# mipi_deserializer_poc.net
KiCad netlist of a schematic drawn in Altium Designer
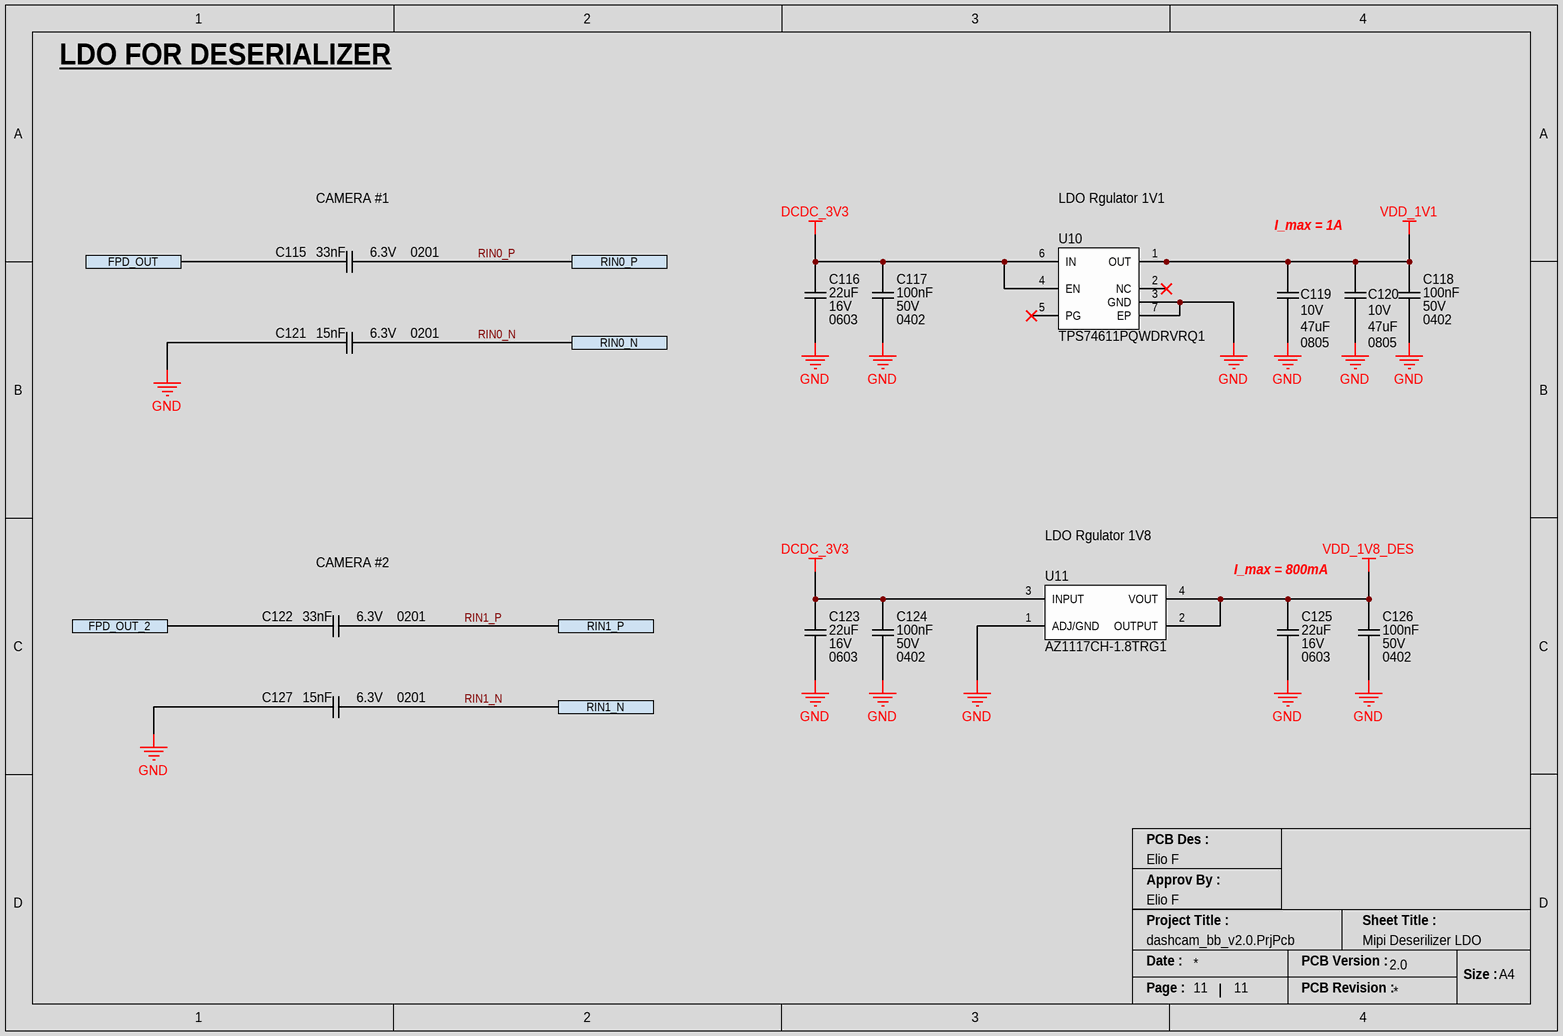
[diagram p0: mipi_deserializer_poc.SchDoc]

(export (version "E")
  (design (tool "Eeschema 10.0.6"))
  (components
    (comp (ref "C115")
      (value "GRM033R60J333KE01D")
      (footprint "CAP_0201_CAPC0603X03N")
      (description "Multilayer Ceramic Capacitor, 0.033 uF, 6.3 V, ± 10%, X5R, 0201 [0603 Metric]")
      (fields
        (field (name "MANUFACTURER") "Murata")
        (field (name "TOLERANCE") "10%")
        (field (name "VOLTAGE RATING") "6.3V")
        (field (name "CAPACITANCE") "33nF")
        (field (name "CASE/PACKAGE") "0201")
      )
      (libsource (lib "Electronic Devices_LIB") (part "CAP_0.033uF_6.3V_X5R_0201"))
    )
    (comp (ref "C116")
      (value "CL10A226MO7JZNC")
      (footprint "CAP_0603_CAPC1608X08N")
      (description "Cap Ceramic 22uF 16V X5R 20% Pad SMD 0603 85C T/R")
      (fields
        (field (name "MANUFACTURER") "Samsung")
        (field (name "TOLERANCE") "20%")
        (field (name "CAPACITANCE") "22uF")
        (field (name "VOLTAGE RATING") "16V")
        (field (name "CASE/PACKAGE") "0603")
      )
      (libsource (lib "Electronic Devices_LIB") (part "CAP_22UF_16V_X5R_0603"))
    )
    (comp (ref "C117")
      (value "GRM155R71H104KE14D")
      (footprint "CAP_0402_CAPC1005X05N")
      (description "Multilayer Ceramic Capacitor, 0.1 uF, 16 V, ± 10%, X7R, 0402 [1005 Metric]")
      (fields
        (field (name "MANUFACTURER") "Murata")
        (field (name "TOLERANCE") "10%")
        (field (name "VOLTAGE RATING") "50V")
        (field (name "CAPACITANCE") "100nF")
        (field (name "CASE/PACKAGE") "0402")
      )
      (libsource (lib "Electronic Devices_LIB") (part "CAP_100NF_50V_X7R_0402"))
    )
    (comp (ref "C118")
      (value "GRM155R71H104KE14D")
      (footprint "CAP_0402_CAPC1005X05N")
      (description "Multilayer Ceramic Capacitor, 0.1 uF, 16 V, ± 10%, X7R, 0402 [1005 Metric]")
      (fields
        (field (name "MANUFACTURER") "Murata")
        (field (name "TOLERANCE") "10%")
        (field (name "VOLTAGE RATING") "50V")
        (field (name "CAPACITANCE") "100nF")
        (field (name "CASE/PACKAGE") "0402")
      )
      (libsource (lib "Electronic Devices_LIB") (part "CAP_100NF_50V_X7R_0402"))
    )
    (comp (ref "C119")
      (value "C2012X5R1A476M125AC")
      (footprint "CAP_0805_CAPC2012X12N")
      (description "Multilayer Ceramic Capacitor, 47 uF, 10 V, ± 20%, X5R, 0805 [2012 Metric]")
      (fields
        (field (name "MANUFACTURER") "TDK")
        (field (name "TOLERANCE") "20%")
        (field (name "VOLTAGE RATING (DC)") "10V")
        (field (name "CAPACITANCE") "47uF")
        (field (name "CASE CODE (IMPERIAL)") "0805")
      )
      (libsource (lib "Electronic Devices_LIB") (part "CAP_47UF_10V_X5R_0805"))
    )
    (comp (ref "C120")
      (value "C2012X5R1A476M125AC")
      (footprint "CAP_0805_CAPC2012X12N")
      (description "Multilayer Ceramic Capacitor, 47 uF, 10 V, ± 20%, X5R, 0805 [2012 Metric]")
      (fields
        (field (name "MANUFACTURER") "TDK")
        (field (name "TOLERANCE") "20%")
        (field (name "VOLTAGE RATING (DC)") "10V")
        (field (name "CAPACITANCE") "47uF")
        (field (name "CASE CODE (IMPERIAL)") "0805")
      )
      (libsource (lib "Electronic Devices_LIB") (part "CAP_47UF_10V_X5R_0805"))
    )
    (comp (ref "C121")
      (value "GRM033R60J153KE01D")
      (footprint "CAP_0201_CAPC0603X03N")
      (description "0201 15 nF 6.3 V ±10% Tolerance X5R SMT Multilayer Ceramic Capacitor")
      (fields
        (field (name "MANUFACTURER") "Murata")
        (field (name "TOLERANCE") "10%")
        (field (name "VOLTAGE RATING") "6.3V")
        (field (name "CAPACITANCE") "15nF")
        (field (name "CASE/PACKAGE") "0201")
      )
      (libsource (lib "Electronic Devices_LIB") (part "CAP_0.015uF_6.3V_X5R_0201"))
    )
    (comp (ref "C122")
      (value "GRM033R60J333KE01D")
      (footprint "CAP_0201_CAPC0603X03N")
      (description "Multilayer Ceramic Capacitor, 0.033 uF, 6.3 V, ± 10%, X5R, 0201 [0603 Metric]")
      (fields
        (field (name "MANUFACTURER") "Murata")
        (field (name "TOLERANCE") "10%")
        (field (name "VOLTAGE RATING") "6.3V")
        (field (name "CAPACITANCE") "33nF")
        (field (name "CASE/PACKAGE") "0201")
      )
      (libsource (lib "Electronic Devices_LIB") (part "CAP_0.033uF_6.3V_X5R_0201"))
    )
    (comp (ref "C123")
      (value "CL10A226MO7JZNC")
      (footprint "CAP_0603_CAPC1608X08N")
      (description "Cap Ceramic 22uF 16V X5R 20% Pad SMD 0603 85C T/R")
      (fields
        (field (name "MANUFACTURER") "Samsung")
        (field (name "TOLERANCE") "20%")
        (field (name "CAPACITANCE") "22uF")
        (field (name "VOLTAGE RATING") "16V")
        (field (name "CASE/PACKAGE") "0603")
      )
      (libsource (lib "Electronic Devices_LIB") (part "CAP_22UF_16V_X5R_0603"))
    )
    (comp (ref "C124")
      (value "GRM155R71H104KE14D")
      (footprint "CAP_0402_CAPC1005X05N")
      (description "Multilayer Ceramic Capacitor, 0.1 uF, 16 V, ± 10%, X7R, 0402 [1005 Metric]")
      (fields
        (field (name "MANUFACTURER") "Murata")
        (field (name "TOLERANCE") "10%")
        (field (name "VOLTAGE RATING") "50V")
        (field (name "CAPACITANCE") "100nF")
        (field (name "CASE/PACKAGE") "0402")
      )
      (libsource (lib "Electronic Devices_LIB") (part "CAP_100NF_50V_X7R_0402"))
    )
    (comp (ref "C125")
      (value "CL10A226MO7JZNC")
      (footprint "CAP_0603_CAPC1608X08N")
      (description "Cap Ceramic 22uF 16V X5R 20% Pad SMD 0603 85C T/R")
      (fields
        (field (name "MANUFACTURER") "Samsung")
        (field (name "TOLERANCE") "20%")
        (field (name "CAPACITANCE") "22uF")
        (field (name "VOLTAGE RATING") "16V")
        (field (name "CASE/PACKAGE") "0603")
      )
      (libsource (lib "Electronic Devices_LIB") (part "CAP_22UF_16V_X5R_0603"))
    )
    (comp (ref "C126")
      (value "GRM155R71H104KE14D")
      (footprint "CAP_0402_CAPC1005X05N")
      (description "Multilayer Ceramic Capacitor, 0.1 uF, 16 V, ± 10%, X7R, 0402 [1005 Metric]")
      (fields
        (field (name "MANUFACTURER") "Murata")
        (field (name "TOLERANCE") "10%")
        (field (name "VOLTAGE RATING") "50V")
        (field (name "CAPACITANCE") "100nF")
        (field (name "CASE/PACKAGE") "0402")
      )
      (libsource (lib "Electronic Devices_LIB") (part "CAP_100NF_50V_X7R_0402"))
    )
    (comp (ref "C127")
      (value "GRM033R60J153KE01D")
      (footprint "CAP_0201_CAPC0603X03N")
      (description "0201 15 nF 6.3 V ±10% Tolerance X5R SMT Multilayer Ceramic Capacitor")
      (fields
        (field (name "MANUFACTURER") "Murata")
        (field (name "TOLERANCE") "10%")
        (field (name "VOLTAGE RATING") "6.3V")
        (field (name "CAPACITANCE") "15nF")
        (field (name "CASE/PACKAGE") "0201")
      )
      (libsource (lib "Electronic Devices_LIB") (part "CAP_0.015uF_6.3V_X5R_0201"))
    )
    (comp (ref "U10")
      (value "TPS74611PQWDRVRQ1")
      (footprint "IC_REG_LDO_1.1V_SON65P200X200X80-7N")
      (description "Voltage Regulator; linear, LDO; fixed; Vout: 1.1V; Vin: 1.5-6V; 1A; -40+125 deg.C; SMD; WSON6")
      (fields (field (name "MANUFACTURER") "Texas Instruments"))
      (libsource (lib "Electronic Devices_LIB") (part "IC_REG_LDO_1.1V_1A_TPS74611PQWDRVRQ1"))
    )
    (comp (ref "U11")
      (value "AZ1117CH-1.8TRG1")
      (footprint "SOT230P700X180-4N")
      (description "AZ1117C Series 1.8 V 800 mA Fixed Surface Mount Voltage Regulator - SOT-223")
      (fields (field (name "MANUFACTURER") "Diodes"))
      (libsource (lib "Electronic Devices_LIB") (part "IC_REG_LDO_1.8_1A_AZ1117CH-1.8TRG1"))
    )
  )
  (nets
    (net (code "1") (name "/FPD_OUT") (class "Default")
      (node (ref "C115") (pin "1") (pinfunction "1_1") (pintype "passive"))
    )
    (net (code "2") (name "/FPD_OUT_2") (class "Default")
      (node (ref "C122") (pin "1") (pinfunction "1_1") (pintype "passive"))
    )
    (net (code "3") (name "/RIN0_N") (class "Default")
      (node (ref "C121") (pin "2") (pinfunction "2_2") (pintype "passive"))
    )
    (net (code "4") (name "/RIN0_P") (class "Default")
      (node (ref "C115") (pin "2") (pinfunction "2_2") (pintype "passive"))
    )
    (net (code "5") (name "/RIN1_N") (class "Default")
      (node (ref "C127") (pin "2") (pinfunction "2_2") (pintype "passive"))
    )
    (net (code "6") (name "/RIN1_P") (class "Default")
      (node (ref "C122") (pin "2") (pinfunction "2_2") (pintype "passive"))
    )
    (net (code "7") (name "DCDC_3V3") (class "Default")
      (node (ref "C116") (pin "2") (pinfunction "2_2") (pintype "passive"))
      (node (ref "C117") (pin "2") (pinfunction "2_2") (pintype "passive"))
      (node (ref "C123") (pin "2") (pinfunction "2_2") (pintype "passive"))
      (node (ref "C124") (pin "2") (pinfunction "2_2") (pintype "passive"))
      (node (ref "U10") (pin "4") (pinfunction "EN_4") (pintype "passive"))
      (node (ref "U10") (pin "6") (pinfunction "IN_6") (pintype "passive"))
      (node (ref "U11") (pin "3") (pinfunction "INPUT_3") (pintype "passive"))
    )
    (net (code "8") (name "GND") (class "Default")
      (node (ref "C116") (pin "1") (pinfunction "1_1") (pintype "passive"))
      (node (ref "C117") (pin "1") (pinfunction "1_1") (pintype "passive"))
      (node (ref "C118") (pin "1") (pinfunction "1_1") (pintype "passive"))
      (node (ref "C119") (pin "1") (pinfunction "1_1") (pintype "passive"))
      (node (ref "C120") (pin "1") (pinfunction "1_1") (pintype "passive"))
      (node (ref "C121") (pin "1") (pinfunction "1_1") (pintype "passive"))
      (node (ref "C123") (pin "1") (pinfunction "1_1") (pintype "passive"))
      (node (ref "C124") (pin "1") (pinfunction "1_1") (pintype "passive"))
      (node (ref "C125") (pin "1") (pinfunction "1_1") (pintype "passive"))
      (node (ref "C126") (pin "1") (pinfunction "1_1") (pintype "passive"))
      (node (ref "C127") (pin "1") (pinfunction "1_1") (pintype "passive"))
      (node (ref "U10") (pin "3") (pinfunction "GND_3") (pintype "passive"))
      (node (ref "U10") (pin "7") (pinfunction "EP_7") (pintype "passive"))
      (node (ref "U11") (pin "1") (pinfunction "ADJ/GND_1") (pintype "passive"))
    )
    (net (code "9") (name "VDD_1V1") (class "Default")
      (node (ref "C118") (pin "2") (pinfunction "2_2") (pintype "passive"))
      (node (ref "C119") (pin "2") (pinfunction "2_2") (pintype "passive"))
      (node (ref "C120") (pin "2") (pinfunction "2_2") (pintype "passive"))
      (node (ref "U10") (pin "1") (pinfunction "OUT_1") (pintype "passive"))
    )
    (net (code "10") (name "VDD_1V8_DES") (class "Default")
      (node (ref "C125") (pin "2") (pinfunction "2_2") (pintype "passive"))
      (node (ref "C126") (pin "2") (pinfunction "2_2") (pintype "passive"))
      (node (ref "U11") (pin "2") (pinfunction "OUTPUT_2") (pintype "passive"))
      (node (ref "U11") (pin "4") (pinfunction "VOUT_4") (pintype "passive"))
    )
    (net (code "11") (name "unconnected-(U10-NC-Pad2)") (class "Default")
      (node (ref "U10") (pin "2") (pinfunction "NC_2") (pintype "passive+no_connect"))
    )
    (net (code "12") (name "unconnected-(U10-PG-Pad5)") (class "Default")
      (node (ref "U10") (pin "5") (pinfunction "PG_5") (pintype "passive+no_connect"))
    )
  )
)
